# BaseBoardSch.net
KiCad netlist of a schematic drawn in Altium Designer
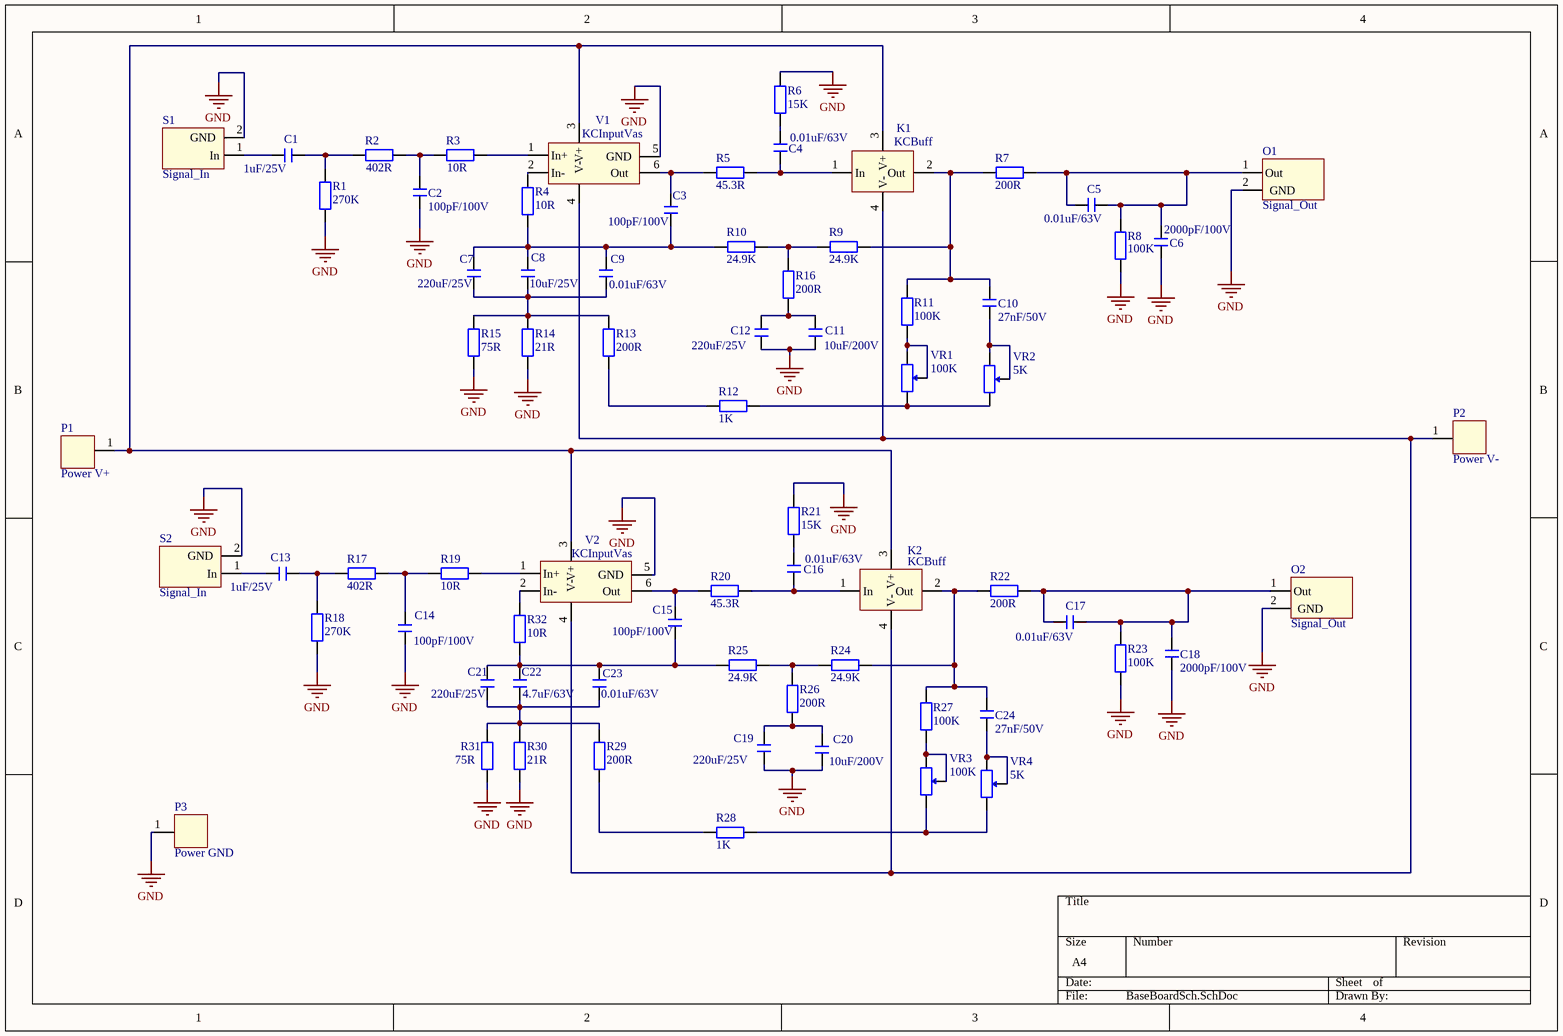
[diagram p0: BaseBoardSch.SchDoc]

(export (version "E")
  (design (tool "Eeschema 10.0.6"))
  (components
    (comp (ref "C1")
      (value "1uF/25V")
      (footprint "CBB 20*23*17")
      (description "CBB电容")
      (fields (field (name "版权归属") "源创客"))
      (libsource (lib "电阻-电容-电感") (part "C-CBB"))
    )
    (comp (ref "C2")
      (value "100pF/100V")
      (footprint "CBB 20*23*17")
      (description "CBB电容")
      (fields (field (name "版权归属") "源创客"))
      (libsource (lib "电阻-电容-电感") (part "C-CBB"))
    )
    (comp (ref "C3")
      (value "100pF/100V")
      (footprint "CBB 10*12*8")
      (description "CBB电容")
      (fields (field (name "版权归属") "源创客"))
      (libsource (lib "电阻-电容-电感") (part "C-CBB"))
    )
    (comp (ref "C4")
      (value "0.01uF/63V")
      (footprint "CBB 10*12*8")
      (description "CBB电容")
      (fields (field (name "版权归属") "源创客"))
      (libsource (lib "电阻-电容-电感") (part "C-CBB"))
    )
    (comp (ref "C5")
      (value "0.01uF/63V")
      (footprint "CBB 10*12*8")
      (description "CBB电容")
      (fields (field (name "版权归属") "源创客"))
      (libsource (lib "电阻-电容-电感") (part "C-CBB"))
    )
    (comp (ref "C6")
      (value "2000pF/100V")
      (footprint "CBB 10*12*8")
      (description "CBB电容")
      (fields (field (name "版权归属") "源创客"))
      (libsource (lib "电阻-电容-电感") (part "C-CBB"))
    )
    (comp (ref "C7")
      (value "220uF/25V")
      (footprint "CBB 10*12*8")
      (description "CBB电容")
      (fields (field (name "版权归属") "源创客"))
      (libsource (lib "电阻-电容-电感") (part "C-CBB"))
    )
    (comp (ref "C8")
      (value "10uF/25V")
      (footprint "CBB 10*12*8")
      (description "CBB电容")
      (fields (field (name "版权归属") "源创客"))
      (libsource (lib "电阻-电容-电感") (part "C-CBB"))
    )
    (comp (ref "C9")
      (value "0.01uF/63V")
      (footprint "CBB 10*12*8")
      (description "CBB电容")
      (fields (field (name "版权归属") "源创客"))
      (libsource (lib "电阻-电容-电感") (part "C-CBB"))
    )
    (comp (ref "C10")
      (value "27nF/50V")
      (footprint "CBB 10*12*8")
      (description "CBB电容")
      (fields (field (name "版权归属") "源创客"))
      (libsource (lib "电阻-电容-电感") (part "C-CBB"))
    )
    (comp (ref "C11")
      (value "10uF/200V")
      (footprint "CBB 10*12*8")
      (description "CBB电容")
      (fields (field (name "版权归属") "源创客"))
      (libsource (lib "电阻-电容-电感") (part "C-CBB"))
    )
    (comp (ref "C12")
      (value "220uF/25V")
      (footprint "CBB 10*12*8")
      (description "CBB电容")
      (fields (field (name "版权归属") "源创客"))
      (libsource (lib "电阻-电容-电感") (part "C-CBB"))
    )
    (comp (ref "C13")
      (value "1uF/25V")
      (footprint "CBB 10*12*8")
      (description "CBB电容")
      (fields (field (name "版权归属") "源创客"))
      (libsource (lib "电阻-电容-电感") (part "C-CBB"))
    )
    (comp (ref "C14")
      (value "100pF/100V")
      (footprint "CBB 10*12*8")
      (description "CBB电容")
      (fields (field (name "版权归属") "源创客"))
      (libsource (lib "电阻-电容-电感") (part "C-CBB"))
    )
    (comp (ref "C15")
      (value "100pF/100V")
      (footprint "CBB 10*12*8")
      (description "CBB电容")
      (fields (field (name "版权归属") "源创客"))
      (libsource (lib "电阻-电容-电感") (part "C-CBB"))
    )
    (comp (ref "C16")
      (value "0.01uF/63V")
      (footprint "CBB 10*12*8")
      (description "CBB电容")
      (fields (field (name "版权归属") "源创客"))
      (libsource (lib "电阻-电容-电感") (part "C-CBB"))
    )
    (comp (ref "C17")
      (value "0.01uF/63V")
      (footprint "CBB 10*12*8")
      (description "CBB电容")
      (fields (field (name "版权归属") "源创客"))
      (libsource (lib "电阻-电容-电感") (part "C-CBB"))
    )
    (comp (ref "C18")
      (value "2000pF/100V")
      (footprint "CBB 10*12*8")
      (description "CBB电容")
      (fields (field (name "版权归属") "源创客"))
      (libsource (lib "电阻-电容-电感") (part "C-CBB"))
    )
    (comp (ref "C19")
      (value "220uF/25V")
      (footprint "CBB 10*12*8")
      (description "CBB电容")
      (fields (field (name "版权归属") "源创客"))
      (libsource (lib "电阻-电容-电感") (part "C-CBB"))
    )
    (comp (ref "C20")
      (value "10uF/200V")
      (footprint "CBB 10*12*8")
      (description "CBB电容")
      (fields (field (name "版权归属") "源创客"))
      (libsource (lib "电阻-电容-电感") (part "C-CBB"))
    )
    (comp (ref "C21")
      (value "220uF/25V")
      (footprint "CBB 10*12*8")
      (description "CBB电容")
      (fields (field (name "版权归属") "源创客"))
      (libsource (lib "电阻-电容-电感") (part "C-CBB"))
    )
    (comp (ref "C22")
      (value "4.7uF/63V")
      (footprint "CBB 10*12*8")
      (description "CBB电容")
      (fields (field (name "版权归属") "源创客"))
      (libsource (lib "电阻-电容-电感") (part "C-CBB"))
    )
    (comp (ref "C23")
      (value "0.01uF/63V")
      (footprint "CBB 10*12*8")
      (description "CBB电容")
      (fields (field (name "版权归属") "源创客"))
      (libsource (lib "电阻-电容-电感") (part "C-CBB"))
    )
    (comp (ref "C24")
      (value "27nF/50V")
      (footprint "CBB 10*12*8")
      (description "CBB电容")
      (fields (field (name "版权归属") "源创客"))
      (libsource (lib "电阻-电容-电感") (part "C-CBB"))
    )
    (comp (ref "K1")
      (value "KCBuff")
      (footprint "KCBuff")
      (description "King Cello Buffer Stage")
      (libsource (lib "KC_amp") (part "KCBuff"))
    )
    (comp (ref "K2")
      (value "KCBuff")
      (footprint "KCBuff")
      (description "King Cello Buffer Stage")
      (libsource (lib "KC_amp") (part "KCBuff"))
    )
    (comp (ref "O1")
      (value "Signal_Out")
      (footprint "Signal_Terminal")
      (description "Signal Out")
      (libsource (lib "KC_amp") (part "Signal_Out"))
    )
    (comp (ref "O2")
      (value "Signal_Out")
      (footprint "Signal_Terminal")
      (description "Signal Out")
      (libsource (lib "KC_amp") (part "Signal_Out"))
    )
    (comp (ref "P1")
      (value "Power V+")
      (footprint "SinglePin")
      (description "Power Pin")
      (libsource (lib "KC_amp") (part "PowerPin"))
    )
    (comp (ref "P2")
      (value "Power V-")
      (footprint "SinglePin")
      (description "Power Pin")
      (libsource (lib "") (part "PowerPin_1"))
    )
    (comp (ref "P3") (value "Power GND") (footprint "SinglePin") (libsource (lib "") (part "PowerPin_1")))
    (comp (ref "R1")
      (value "270K")
      (footprint "RS 1/4W")
      (description "直插色环电阻")
      (fields (field (name "版权归属") "源创客"))
      (libsource (lib "电阻-电容-电感") (part "R-CRR"))
    )
    (comp (ref "R2")
      (value "402R")
      (footprint "RS 1/4W")
      (description "直插色环电阻")
      (fields (field (name "版权归属") "源创客"))
      (libsource (lib "电阻-电容-电感") (part "R-CRR"))
    )
    (comp (ref "R3")
      (value "10R")
      (footprint "RS 1/4W")
      (description "直插色环电阻")
      (fields (field (name "版权归属") "源创客"))
      (libsource (lib "电阻-电容-电感") (part "R-CRR"))
    )
    (comp (ref "R4")
      (value "10R")
      (footprint "RS 1/4W")
      (description "直插色环电阻")
      (fields (field (name "版权归属") "源创客"))
      (libsource (lib "电阻-电容-电感") (part "R-CRR"))
    )
    (comp (ref "R5")
      (value "45.3R")
      (footprint "RS 1/4W")
      (description "直插色环电阻")
      (fields (field (name "版权归属") "源创客"))
      (libsource (lib "电阻-电容-电感") (part "R-CRR"))
    )
    (comp (ref "R6")
      (value "15K")
      (footprint "RS 1/4W")
      (description "直插色环电阻")
      (fields (field (name "版权归属") "源创客"))
      (libsource (lib "电阻-电容-电感") (part "R-CRR"))
    )
    (comp (ref "R7")
      (value "200R")
      (footprint "RS 1/4W")
      (description "直插色环电阻")
      (fields (field (name "版权归属") "源创客"))
      (libsource (lib "电阻-电容-电感") (part "R-CRR"))
    )
    (comp (ref "R8")
      (value "100K")
      (footprint "RS 1/4W")
      (description "直插色环电阻")
      (fields (field (name "版权归属") "源创客"))
      (libsource (lib "电阻-电容-电感") (part "R-CRR"))
    )
    (comp (ref "R9")
      (value "24.9K")
      (footprint "RS 1/4W")
      (description "直插色环电阻")
      (fields (field (name "版权归属") "源创客"))
      (libsource (lib "电阻-电容-电感") (part "R-CRR"))
    )
    (comp (ref "R10")
      (value "24.9K")
      (footprint "RS 1/4W")
      (description "直插色环电阻")
      (fields (field (name "版权归属") "源创客"))
      (libsource (lib "电阻-电容-电感") (part "R-CRR"))
    )
    (comp (ref "R11")
      (value "100K")
      (footprint "RS 1/4W")
      (description "直插色环电阻")
      (fields (field (name "版权归属") "源创客"))
      (libsource (lib "电阻-电容-电感") (part "R-CRR"))
    )
    (comp (ref "R12")
      (value "1K")
      (footprint "RS 1/4W")
      (description "直插色环电阻")
      (fields (field (name "版权归属") "源创客"))
      (libsource (lib "电阻-电容-电感") (part "R-CRR"))
    )
    (comp (ref "R13")
      (value "200R")
      (footprint "RS 1/4W")
      (description "直插色环电阻")
      (fields (field (name "版权归属") "源创客"))
      (libsource (lib "电阻-电容-电感") (part "R-CRR"))
    )
    (comp (ref "R14")
      (value "21R")
      (footprint "RS 1/4W")
      (description "直插色环电阻")
      (fields (field (name "版权归属") "源创客"))
      (libsource (lib "电阻-电容-电感") (part "R-CRR"))
    )
    (comp (ref "R15")
      (value "75R")
      (footprint "RS 1/4W")
      (description "直插色环电阻")
      (fields (field (name "版权归属") "源创客"))
      (libsource (lib "电阻-电容-电感") (part "R-CRR"))
    )
    (comp (ref "R16")
      (value "200R")
      (footprint "RS 1/4W")
      (description "直插色环电阻")
      (fields (field (name "版权归属") "源创客"))
      (libsource (lib "电阻-电容-电感") (part "R-CRR"))
    )
    (comp (ref "R17")
      (value "402R")
      (footprint "RS 1/4W")
      (description "直插色环电阻")
      (fields (field (name "版权归属") "源创客"))
      (libsource (lib "电阻-电容-电感") (part "R-CRR"))
    )
    (comp (ref "R18")
      (value "270K")
      (footprint "RS 1/4W")
      (description "直插色环电阻")
      (fields (field (name "版权归属") "源创客"))
      (libsource (lib "电阻-电容-电感") (part "R-CRR"))
    )
    (comp (ref "R19")
      (value "10R")
      (footprint "RS 1/4W")
      (description "直插色环电阻")
      (fields (field (name "版权归属") "源创客"))
      (libsource (lib "电阻-电容-电感") (part "R-CRR"))
    )
    (comp (ref "R20")
      (value "45.3R")
      (footprint "RS 1/4W")
      (description "直插色环电阻")
      (fields (field (name "版权归属") "源创客"))
      (libsource (lib "电阻-电容-电感") (part "R-CRR"))
    )
    (comp (ref "R21")
      (value "15K")
      (footprint "RS 1/4W")
      (description "直插色环电阻")
      (fields (field (name "版权归属") "源创客"))
      (libsource (lib "电阻-电容-电感") (part "R-CRR"))
    )
    (comp (ref "R22")
      (value "200R")
      (footprint "RS 1/4W")
      (description "直插色环电阻")
      (fields (field (name "版权归属") "源创客"))
      (libsource (lib "电阻-电容-电感") (part "R-CRR"))
    )
    (comp (ref "R23")
      (value "100K")
      (footprint "RS 1/4W")
      (description "直插色环电阻")
      (fields (field (name "版权归属") "源创客"))
      (libsource (lib "电阻-电容-电感") (part "R-CRR"))
    )
    (comp (ref "R24")
      (value "24.9K")
      (footprint "RS 1/4W")
      (description "直插色环电阻")
      (fields (field (name "版权归属") "源创客"))
      (libsource (lib "电阻-电容-电感") (part "R-CRR"))
    )
    (comp (ref "R25")
      (value "24.9K")
      (footprint "RS 1/4W")
      (description "直插色环电阻")
      (fields (field (name "版权归属") "源创客"))
      (libsource (lib "电阻-电容-电感") (part "R-CRR"))
    )
    (comp (ref "R26")
      (value "200R")
      (footprint "RS 1/4W")
      (description "直插色环电阻")
      (fields (field (name "版权归属") "源创客"))
      (libsource (lib "电阻-电容-电感") (part "R-CRR"))
    )
    (comp (ref "R27")
      (value "100K")
      (footprint "RS 1/4W")
      (description "直插色环电阻")
      (fields (field (name "版权归属") "源创客"))
      (libsource (lib "电阻-电容-电感") (part "R-CRR"))
    )
    (comp (ref "R28")
      (value "1K")
      (footprint "RS 1/4W")
      (description "直插色环电阻")
      (fields (field (name "版权归属") "源创客"))
      (libsource (lib "电阻-电容-电感") (part "R-CRR"))
    )
    (comp (ref "R29")
      (value "200R")
      (footprint "RS 1/4W")
      (description "直插色环电阻")
      (fields (field (name "版权归属") "源创客"))
      (libsource (lib "电阻-电容-电感") (part "R-CRR"))
    )
    (comp (ref "R30")
      (value "21R")
      (footprint "RS 1/4W")
      (description "直插色环电阻")
      (fields (field (name "版权归属") "源创客"))
      (libsource (lib "电阻-电容-电感") (part "R-CRR"))
    )
    (comp (ref "R31")
      (value "75R")
      (footprint "RS 1/4W")
      (description "直插色环电阻")
      (fields (field (name "版权归属") "源创客"))
      (libsource (lib "电阻-电容-电感") (part "R-CRR"))
    )
    (comp (ref "R32")
      (value "10R")
      (footprint "RS 1/4W")
      (description "直插色环电阻")
      (fields (field (name "版权归属") "源创客"))
      (libsource (lib "电阻-电容-电感") (part "R-CRR"))
    )
    (comp (ref "S1")
      (value "Signal_In")
      (footprint "Signal_Terminal")
      (description "Signal In")
      (libsource (lib "KC_amp") (part "Signal_In"))
    )
    (comp (ref "S2")
      (value "Signal_In")
      (footprint "Signal_Terminal")
      (description "Signal In")
      (libsource (lib "KC_amp") (part "Signal_In"))
    )
    (comp (ref "V1")
      (value "KCInputVas")
      (footprint "KCIn_VAS")
      (description "King Cello Input Stage and VAS")
      (libsource (lib "KC_amp") (part "KCInputVas"))
    )
    (comp (ref "V2")
      (value "KCInputVas")
      (footprint "KCIn_VAS")
      (description "King Cello Input Stage and VAS")
      (libsource (lib "KC_amp") (part "KCInputVas"))
    )
    (comp (ref "VR1")
      (value "100K")
      (footprint "RS 1/2W-VR")
      (description "直插可调电阻-顶调")
      (libsource (lib "电阻-电容-电感") (part "VR-W"))
    )
    (comp (ref "VR2")
      (value "5K")
      (footprint "RS 1/2W-VR")
      (description "直插可调电阻-顶调")
      (libsource (lib "电阻-电容-电感") (part "VR-W"))
    )
    (comp (ref "VR3")
      (value "100K")
      (footprint "RS 1/2W-VR")
      (description "直插可调电阻-顶调")
      (libsource (lib "电阻-电容-电感") (part "VR-W"))
    )
    (comp (ref "VR4")
      (value "5K")
      (footprint "RS 1/2W-VR")
      (description "直插可调电阻-顶调")
      (libsource (lib "电阻-电容-电感") (part "VR-W"))
    )
  )
  (nets
    (net (code "1") (name "GND") (class "Default")
      (node (ref "C11") (pin "1") (pinfunction "1_1") (pintype "passive"))
      (node (ref "C12") (pin "1") (pinfunction "1_1") (pintype "passive"))
      (node (ref "C14") (pin "1") (pinfunction "1_1") (pintype "passive"))
      (node (ref "C18") (pin "2") (pinfunction "2_2") (pintype "passive"))
      (node (ref "C19") (pin "2") (pinfunction "2_2") (pintype "passive"))
      (node (ref "C2") (pin "1") (pinfunction "1_1") (pintype "passive"))
      (node (ref "C20") (pin "2") (pinfunction "2_2") (pintype "passive"))
      (node (ref "C6") (pin "1") (pinfunction "1_1") (pintype "passive"))
      (node (ref "O1") (pin "2") (pinfunction "GND_2") (pintype "passive"))
      (node (ref "O2") (pin "2") (pinfunction "GND_2") (pintype "passive"))
      (node (ref "P3") (pin "1") (pintype "passive"))
      (node (ref "R1") (pin "1") (pinfunction "1_1") (pintype "passive"))
      (node (ref "R14") (pin "1") (pinfunction "1_1") (pintype "passive"))
      (node (ref "R15") (pin "1") (pinfunction "1_1") (pintype "passive"))
      (node (ref "R18") (pin "1") (pinfunction "1_1") (pintype "passive"))
      (node (ref "R21") (pin "2") (pinfunction "2_2") (pintype "passive"))
      (node (ref "R23") (pin "2") (pinfunction "2_2") (pintype "passive"))
      (node (ref "R30") (pin "1") (pinfunction "1_1") (pintype "passive"))
      (node (ref "R31") (pin "1") (pinfunction "1_1") (pintype "passive"))
      (node (ref "R6") (pin "1") (pinfunction "1_1") (pintype "passive"))
      (node (ref "R8") (pin "1") (pinfunction "1_1") (pintype "passive"))
      (node (ref "S1") (pin "2") (pinfunction "GND_2") (pintype "passive"))
      (node (ref "S2") (pin "2") (pinfunction "GND_2") (pintype "passive"))
      (node (ref "V1") (pin "5") (pinfunction "GND_5") (pintype "passive"))
      (node (ref "V2") (pin "5") (pinfunction "GND_5") (pintype "passive"))
    )
    (net (code "2") (name "Net-(C1-Pad2)") (class "Default")
      (node (ref "C1") (pin "2") (pinfunction "2_2") (pintype "passive"))
      (node (ref "R1") (pin "2") (pinfunction "2_2") (pintype "passive"))
      (node (ref "R2") (pin "1") (pinfunction "1_1") (pintype "passive"))
    )
    (net (code "3") (name "Net-(C2-Pad2)") (class "Default")
      (node (ref "C2") (pin "2") (pinfunction "2_2") (pintype "passive"))
      (node (ref "R2") (pin "2") (pinfunction "2_2") (pintype "passive"))
      (node (ref "R3") (pin "2") (pinfunction "2_2") (pintype "passive"))
    )
    (net (code "4") (name "Net-(C3-Pad1)") (class "Default")
      (node (ref "C3") (pin "1") (pinfunction "1_1") (pintype "passive"))
      (node (ref "C7") (pin "2") (pinfunction "2_2") (pintype "passive"))
      (node (ref "C8") (pin "2") (pinfunction "2_2") (pintype "passive"))
      (node (ref "C9") (pin "2") (pinfunction "2_2") (pintype "passive"))
      (node (ref "R10") (pin "2") (pinfunction "2_2") (pintype "passive"))
      (node (ref "R4") (pin "1") (pinfunction "1_1") (pintype "passive"))
    )
    (net (code "5") (name "Net-(C4-Pad2)") (class "Default")
      (node (ref "C4") (pin "2") (pinfunction "2_2") (pintype "passive"))
      (node (ref "R6") (pin "2") (pinfunction "2_2") (pintype "passive"))
    )
    (net (code "6") (name "Net-(C7-Pad1)") (class "Default")
      (node (ref "C7") (pin "1") (pinfunction "1_1") (pintype "passive"))
      (node (ref "C8") (pin "1") (pinfunction "1_1") (pintype "passive"))
      (node (ref "C9") (pin "1") (pinfunction "1_1") (pintype "passive"))
      (node (ref "R13") (pin "2") (pinfunction "2_2") (pintype "passive"))
      (node (ref "R14") (pin "2") (pinfunction "2_2") (pintype "passive"))
      (node (ref "R15") (pin "2") (pinfunction "2_2") (pintype "passive"))
    )
    (net (code "7") (name "Net-(C10-Pad1)") (class "Default")
      (node (ref "C10") (pin "1") (pinfunction "1_1") (pintype "passive"))
      (node (ref "VR2") (pin "1") (pinfunction "1_1") (pintype "passive"))
      (node (ref "VR2") (pin "3") (pinfunction "3_3") (pintype "passive"))
    )
    (net (code "8") (name "Net-(C11-Pad2)") (class "Default")
      (node (ref "C11") (pin "2") (pinfunction "2_2") (pintype "passive"))
      (node (ref "C12") (pin "2") (pinfunction "2_2") (pintype "passive"))
      (node (ref "R16") (pin "1") (pinfunction "1_1") (pintype "passive"))
    )
    (net (code "9") (name "Net-(C13-Pad2)") (class "Default")
      (node (ref "C13") (pin "2") (pinfunction "2_2") (pintype "passive"))
      (node (ref "R17") (pin "1") (pinfunction "1_1") (pintype "passive"))
      (node (ref "R18") (pin "2") (pinfunction "2_2") (pintype "passive"))
    )
    (net (code "10") (name "Net-(C14-Pad2)") (class "Default")
      (node (ref "C14") (pin "2") (pinfunction "2_2") (pintype "passive"))
      (node (ref "R17") (pin "2") (pinfunction "2_2") (pintype "passive"))
      (node (ref "R19") (pin "1") (pinfunction "1_1") (pintype "passive"))
    )
    (net (code "11") (name "Net-(C15-Pad1)") (class "Default")
      (node (ref "C15") (pin "1") (pinfunction "1_1") (pintype "passive"))
      (node (ref "C21") (pin "1") (pinfunction "1_1") (pintype "passive"))
      (node (ref "C22") (pin "1") (pinfunction "1_1") (pintype "passive"))
      (node (ref "C23") (pin "1") (pinfunction "1_1") (pintype "passive"))
      (node (ref "R25") (pin "1") (pinfunction "1_1") (pintype "passive"))
      (node (ref "R32") (pin "1") (pinfunction "1_1") (pintype "passive"))
    )
    (net (code "12") (name "Net-(C16-Pad2)") (class "Default")
      (node (ref "C16") (pin "2") (pinfunction "2_2") (pintype "passive"))
      (node (ref "R21") (pin "1") (pinfunction "1_1") (pintype "passive"))
    )
    (net (code "13") (name "Net-(C19-Pad1)") (class "Default")
      (node (ref "C19") (pin "1") (pinfunction "1_1") (pintype "passive"))
      (node (ref "C20") (pin "1") (pinfunction "1_1") (pintype "passive"))
      (node (ref "R26") (pin "1") (pinfunction "1_1") (pintype "passive"))
    )
    (net (code "14") (name "Net-(C21-Pad2)") (class "Default")
      (node (ref "C21") (pin "2") (pinfunction "2_2") (pintype "passive"))
      (node (ref "C22") (pin "2") (pinfunction "2_2") (pintype "passive"))
      (node (ref "C23") (pin "2") (pinfunction "2_2") (pintype "passive"))
      (node (ref "R29") (pin "2") (pinfunction "2_2") (pintype "passive"))
      (node (ref "R30") (pin "2") (pinfunction "2_2") (pintype "passive"))
      (node (ref "R31") (pin "2") (pinfunction "2_2") (pintype "passive"))
    )
    (net (code "15") (name "Net-(C24-Pad2)") (class "Default")
      (node (ref "C24") (pin "2") (pinfunction "2_2") (pintype "passive"))
      (node (ref "VR4") (pin "1") (pinfunction "1_1") (pintype "passive"))
      (node (ref "VR4") (pin "3") (pinfunction "3_3") (pintype "passive"))
    )
    (net (code "16") (name "Net-(K1-In)") (class "Default")
      (node (ref "C4") (pin "1") (pinfunction "1_1") (pintype "passive"))
      (node (ref "K1") (pin "1") (pinfunction "In_1") (pintype "passive"))
      (node (ref "R5") (pin "1") (pinfunction "1_1") (pintype "passive"))
    )
    (net (code "17") (name "Net-(K1-Out)") (class "Default")
      (node (ref "C10") (pin "2") (pinfunction "2_2") (pintype "passive"))
      (node (ref "K1") (pin "2") (pinfunction "Out_2") (pintype "passive"))
      (node (ref "R11") (pin "1") (pinfunction "1_1") (pintype "passive"))
      (node (ref "R7") (pin "1") (pinfunction "1_1") (pintype "passive"))
      (node (ref "R9") (pin "1") (pinfunction "1_1") (pintype "passive"))
    )
    (net (code "18") (name "Net-(K1-V+)") (class "Default")
      (node (ref "K1") (pin "3") (pinfunction "V+_3") (pintype "passive"))
      (node (ref "K2") (pin "3") (pinfunction "V+_3") (pintype "passive"))
      (node (ref "P1") (pin "1") (pintype "passive"))
      (node (ref "V1") (pin "3") (pinfunction "V+_3") (pintype "passive"))
      (node (ref "V2") (pin "3") (pinfunction "V+_3") (pintype "passive"))
    )
    (net (code "19") (name "Net-(K1-V-)") (class "Default")
      (node (ref "K1") (pin "4") (pinfunction "V-_4") (pintype "passive"))
      (node (ref "K2") (pin "4") (pinfunction "V-_4") (pintype "passive"))
      (node (ref "P2") (pin "1") (pintype "passive"))
      (node (ref "V1") (pin "4") (pinfunction "V-_4") (pintype "passive"))
      (node (ref "V2") (pin "4") (pinfunction "V-_4") (pintype "passive"))
    )
    (net (code "20") (name "Net-(K2-In)") (class "Default")
      (node (ref "C16") (pin "1") (pinfunction "1_1") (pintype "passive"))
      (node (ref "K2") (pin "1") (pinfunction "In_1") (pintype "passive"))
      (node (ref "R20") (pin "2") (pinfunction "2_2") (pintype "passive"))
    )
    (net (code "21") (name "Net-(K2-Out)") (class "Default")
      (node (ref "C24") (pin "1") (pinfunction "1_1") (pintype "passive"))
      (node (ref "K2") (pin "2") (pinfunction "Out_2") (pintype "passive"))
      (node (ref "R22") (pin "2") (pinfunction "2_2") (pintype "passive"))
      (node (ref "R24") (pin "2") (pinfunction "2_2") (pintype "passive"))
      (node (ref "R27") (pin "1") (pinfunction "1_1") (pintype "passive"))
    )
    (net (code "22") (name "Net-(O1-Out)") (class "Default")
      (node (ref "C5") (pin "1") (pinfunction "1_1") (pintype "passive"))
      (node (ref "C5") (pin "2") (pinfunction "2_2") (pintype "passive"))
      (node (ref "C6") (pin "2") (pinfunction "2_2") (pintype "passive"))
      (node (ref "O1") (pin "1") (pinfunction "Out_1") (pintype "passive"))
      (node (ref "R7") (pin "2") (pinfunction "2_2") (pintype "passive"))
      (node (ref "R8") (pin "2") (pinfunction "2_2") (pintype "passive"))
    )
    (net (code "23") (name "Net-(O2-Out)") (class "Default")
      (node (ref "C17") (pin "1") (pinfunction "1_1") (pintype "passive"))
      (node (ref "C17") (pin "2") (pinfunction "2_2") (pintype "passive"))
      (node (ref "C18") (pin "1") (pinfunction "1_1") (pintype "passive"))
      (node (ref "O2") (pin "1") (pinfunction "Out_1") (pintype "passive"))
      (node (ref "R22") (pin "1") (pinfunction "1_1") (pintype "passive"))
      (node (ref "R23") (pin "1") (pinfunction "1_1") (pintype "passive"))
    )
    (net (code "24") (name "Net-(R10-Pad1)") (class "Default")
      (node (ref "R10") (pin "1") (pinfunction "1_1") (pintype "passive"))
      (node (ref "R16") (pin "2") (pinfunction "2_2") (pintype "passive"))
      (node (ref "R9") (pin "2") (pinfunction "2_2") (pintype "passive"))
    )
    (net (code "25") (name "Net-(R11-Pad2)") (class "Default")
      (node (ref "R11") (pin "2") (pinfunction "2_2") (pintype "passive"))
      (node (ref "VR1") (pin "1") (pinfunction "1_1") (pintype "passive"))
      (node (ref "VR1") (pin "3") (pinfunction "3_3") (pintype "passive"))
    )
    (net (code "26") (name "Net-(R12-Pad1)") (class "Default")
      (node (ref "R12") (pin "1") (pinfunction "1_1") (pintype "passive"))
      (node (ref "R13") (pin "1") (pinfunction "1_1") (pintype "passive"))
    )
    (net (code "27") (name "Net-(R12-Pad2)") (class "Default")
      (node (ref "R12") (pin "2") (pinfunction "2_2") (pintype "passive"))
      (node (ref "VR1") (pin "2") (pinfunction "2_2") (pintype "passive"))
      (node (ref "VR2") (pin "2") (pinfunction "2_2") (pintype "passive"))
    )
    (net (code "28") (name "Net-(R24-Pad1)") (class "Default")
      (node (ref "R24") (pin "1") (pinfunction "1_1") (pintype "passive"))
      (node (ref "R25") (pin "2") (pinfunction "2_2") (pintype "passive"))
      (node (ref "R26") (pin "2") (pinfunction "2_2") (pintype "passive"))
    )
    (net (code "29") (name "Net-(R27-Pad2)") (class "Default")
      (node (ref "R27") (pin "2") (pinfunction "2_2") (pintype "passive"))
      (node (ref "VR3") (pin "1") (pinfunction "1_1") (pintype "passive"))
      (node (ref "VR3") (pin "3") (pinfunction "3_3") (pintype "passive"))
    )
    (net (code "30") (name "Net-(R28-Pad1)") (class "Default")
      (node (ref "R28") (pin "1") (pinfunction "1_1") (pintype "passive"))
      (node (ref "R29") (pin "1") (pinfunction "1_1") (pintype "passive"))
    )
    (net (code "31") (name "Net-(R28-Pad2)") (class "Default")
      (node (ref "R28") (pin "2") (pinfunction "2_2") (pintype "passive"))
      (node (ref "VR3") (pin "2") (pinfunction "2_2") (pintype "passive"))
      (node (ref "VR4") (pin "2") (pinfunction "2_2") (pintype "passive"))
    )
    (net (code "32") (name "Net-(S1-In)") (class "Default")
      (node (ref "C1") (pin "1") (pinfunction "1_1") (pintype "passive"))
      (node (ref "S1") (pin "1") (pinfunction "In_1") (pintype "passive"))
    )
    (net (code "33") (name "Net-(S2-In)") (class "Default")
      (node (ref "C13") (pin "1") (pinfunction "1_1") (pintype "passive"))
      (node (ref "S2") (pin "1") (pinfunction "In_1") (pintype "passive"))
    )
    (net (code "34") (name "Net-(V1-In+)") (class "Default")
      (node (ref "R3") (pin "1") (pinfunction "1_1") (pintype "passive"))
      (node (ref "V1") (pin "1") (pinfunction "In+_1") (pintype "passive"))
    )
    (net (code "35") (name "Net-(V1-In-)") (class "Default")
      (node (ref "R4") (pin "2") (pinfunction "2_2") (pintype "passive"))
      (node (ref "V1") (pin "2") (pinfunction "In-_2") (pintype "passive"))
    )
    (net (code "36") (name "Net-(V1-Out)") (class "Default")
      (node (ref "C3") (pin "2") (pinfunction "2_2") (pintype "passive"))
      (node (ref "R5") (pin "2") (pinfunction "2_2") (pintype "passive"))
      (node (ref "V1") (pin "6") (pinfunction "Out_6") (pintype "passive"))
    )
    (net (code "37") (name "Net-(V2-In+)") (class "Default")
      (node (ref "R19") (pin "2") (pinfunction "2_2") (pintype "passive"))
      (node (ref "V2") (pin "1") (pinfunction "In+_1") (pintype "passive"))
    )
    (net (code "38") (name "Net-(V2-In-)") (class "Default")
      (node (ref "R32") (pin "2") (pinfunction "2_2") (pintype "passive"))
      (node (ref "V2") (pin "2") (pinfunction "In-_2") (pintype "passive"))
    )
    (net (code "39") (name "Net-(V2-Out)") (class "Default")
      (node (ref "C15") (pin "2") (pinfunction "2_2") (pintype "passive"))
      (node (ref "R20") (pin "1") (pinfunction "1_1") (pintype "passive"))
      (node (ref "V2") (pin "6") (pinfunction "Out_6") (pintype "passive"))
    )
  )
)
